# Power_Supply.net
KiCad netlist of a schematic drawn in Altium Designer
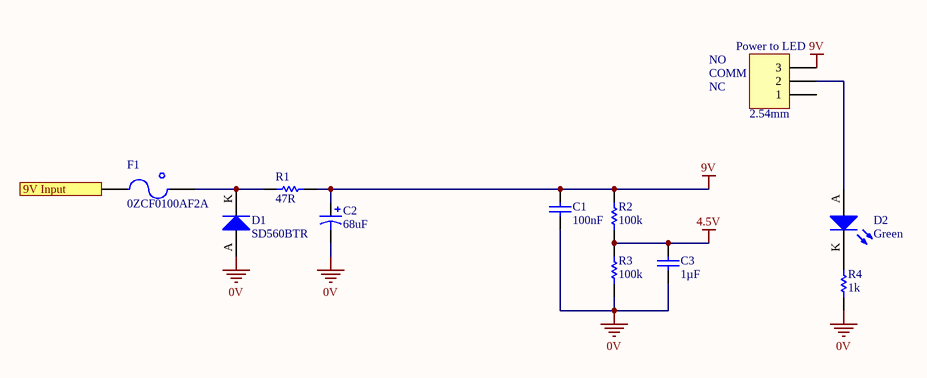
[diagram p0: Power Supply.SchDoc]

(export (version "E")
  (design (tool "Eeschema 10.0.6"))
  (components
    (comp (ref "C1")
      (value "100nF")
      (footprint "0805")
      (fields
        (field (name "PART NUMBER") "GCM21BR71H104KA37L")
        (field (name "TOLERANCE") "±10%")
        (field (name "MANUFACTURER") "muRata")
      )
      (libsource (lib "ts_20-standard-library") (part "Capacitor"))
    )
    (comp (ref "C2")
      (value "~")
      (footprint "2924")
      (fields
        (field (name "PART NUMBER") "TAJV686K035RNJ")
        (field (name "TOLERANCE") "10%")
        (field (name "MANUFACTURER") "AVX Corporation")
      )
      (libsource (lib "ts_20-standard-library") (part "Capacitor (Polarised)"))
    )
    (comp (ref "C3")
      (value "1µF")
      (footprint "0805")
      (fields
        (field (name "PART NUMBER") "GCM21BR71H105KA03L")
        (field (name "TOLERANCE") "±10%")
        (field (name "MANUFACTURER") "muRata")
      )
      (libsource (lib "ts_20-standard-library") (part "Capacitor"))
    )
    (comp (ref "D1")
      (value "SD560BTR")
      (footprint "SMB Diode")
      (description "1.2V_F 600V 5A SMB")
      (fields
        (field (name "MANUFACTURER") "SMC Diode Solutions")
        (field (name "DIGIKEY PART NUMBER") "1655-1530-2-ND")
      )
      (libsource (lib "ts_20-standard-library") (part "Diode"))
    )
    (comp (ref "D2")
      (value "Green")
      (footprint "5MM LED")
      (description "LED GREEN CLEAR 5MM ROUND T/H")
      (fields (field (name "PART NUMBER") "C503B-GAN-CB0F0791") (field (name "MANUFACTURER") "Cree Inc."))
      (libsource (lib "ts_20-standard-library") (part "LED"))
    )
    (comp (ref "F1")
      (value "0ZCF0100AF2A")
      (footprint "2920")
      (description "PTC RESET FUSE 60V 1A 292")
      (fields
        (field (name "MANUFACTURER") "Littelfuse Inc.")
        (field (name "DIGIKEY PART NUMBER") "507-2070-1-ND")
      )
      (libsource (lib "ts_20-standard-library") (part "PTC Fuse"))
    )
    (comp (ref "Power to LED")
      (value "2.54mm")
      (footprint "TH 2.54mm Header 1x3")
      (fields (field (name "PART NUMBER") "TH 2.54mm Header 1x3") (field (name "CONTACT") "NA"))
      (libsource (lib "ts_20-standard-connectors") (part "Header 1x3"))
    )
    (comp (ref "R1")
      (value "47R")
      (footprint "2512")
      (fields
        (field (name "PART NUMBER") "352147RFT")
        (field (name "MANUFACTURER") "TE Connectivity")
        (field (name "TOLERANCE") "0.01")
      )
      (libsource (lib "ts_20-standard-library") (part "Resistor"))
    )
    (comp (ref "R2")
      (value "100k")
      (footprint "0805")
      (fields
        (field (name "PART NUMBER") "RC0805FR07100KL")
        (field (name "MANUFACTURER") "YAGEO")
        (field (name "TOLERANCE") "0.01")
      )
      (libsource (lib "ts_20-standard-library") (part "Resistor"))
    )
    (comp (ref "R3")
      (value "100k")
      (footprint "0805")
      (fields
        (field (name "PART NUMBER") "RC0805FR07100KL")
        (field (name "MANUFACTURER") "YAGEO")
        (field (name "TOLERANCE") "0.01")
      )
      (libsource (lib "ts_20-standard-library") (part "Resistor"))
    )
    (comp (ref "R4")
      (value "1k")
      (footprint "0805")
      (fields
        (field (name "PART NUMBER") "RC0805FR071KL")
        (field (name "MANUFACTURER") "YAGEO")
        (field (name "TOLERANCE") "0.01")
      )
      (libsource (lib "ts_20-standard-library") (part "Resistor"))
    )
  )
  (nets
    (net (code "1") (name "/9V Input") (class "Default")
      (node (ref "F1") (pin "1") (pinfunction "1_1") (pintype "passive"))
    )
    (net (code "2") (name "0V") (class "Default")
      (node (ref "C1") (pin "2") (pinfunction "2_2") (pintype "passive"))
      (node (ref "C2") (pin "1") (pinfunction "1_1") (pintype "passive"))
      (node (ref "C3") (pin "1") (pinfunction "1_1") (pintype "passive"))
      (node (ref "D1") (pin "A") (pinfunction "A_A") (pintype "passive"))
      (node (ref "R3") (pin "1") (pinfunction "1_1") (pintype "passive"))
      (node (ref "R4") (pin "1") (pinfunction "1_1") (pintype "passive"))
    )
    (net (code "3") (name "4.5V") (class "Default")
      (node (ref "C3") (pin "2") (pinfunction "2_2") (pintype "passive"))
      (node (ref "R2") (pin "1") (pinfunction "1_1") (pintype "passive"))
      (node (ref "R3") (pin "2") (pinfunction "2_2") (pintype "passive"))
    )
    (net (code "4") (name "9V") (class "Default")
      (node (ref "C1") (pin "1") (pinfunction "1_1") (pintype "passive"))
      (node (ref "C2") (pin "2") (pinfunction "2_2") (pintype "passive"))
      (node (ref "Power to LED") (pin "3") (pinfunction "3_3") (pintype "passive"))
      (node (ref "R1") (pin "2") (pinfunction "2_2") (pintype "passive"))
      (node (ref "R2") (pin "2") (pinfunction "2_2") (pintype "passive"))
    )
    (net (code "5") (name "Net-(D1-PadK)") (class "Default")
      (node (ref "D1") (pin "K") (pinfunction "K_K") (pintype "passive"))
      (node (ref "F1") (pin "2") (pinfunction "2_2") (pintype "passive"))
      (node (ref "R1") (pin "1") (pinfunction "1_1") (pintype "passive"))
    )
    (net (code "6") (name "Net-(D2-PadA)") (class "Default")
      (node (ref "D2") (pin "A") (pinfunction "A_A") (pintype "passive"))
      (node (ref "Power to LED") (pin "2") (pinfunction "2_2") (pintype "passive"))
    )
    (net (code "7") (name "Net-(D2-PadK)") (class "Default")
      (node (ref "D2") (pin "K") (pinfunction "K_K") (pintype "passive"))
      (node (ref "R4") (pin "2") (pinfunction "2_2") (pintype "passive"))
    )
    (net (code "8") (name "unconnected-(Power to LED-Pad1)") (class "Default")
      (node (ref "Power to LED") (pin "1") (pinfunction "1_1") (pintype "passive"))
    )
  )
)
